# untitled.net
KiCad netlist of a schematic drawn in EAGLE
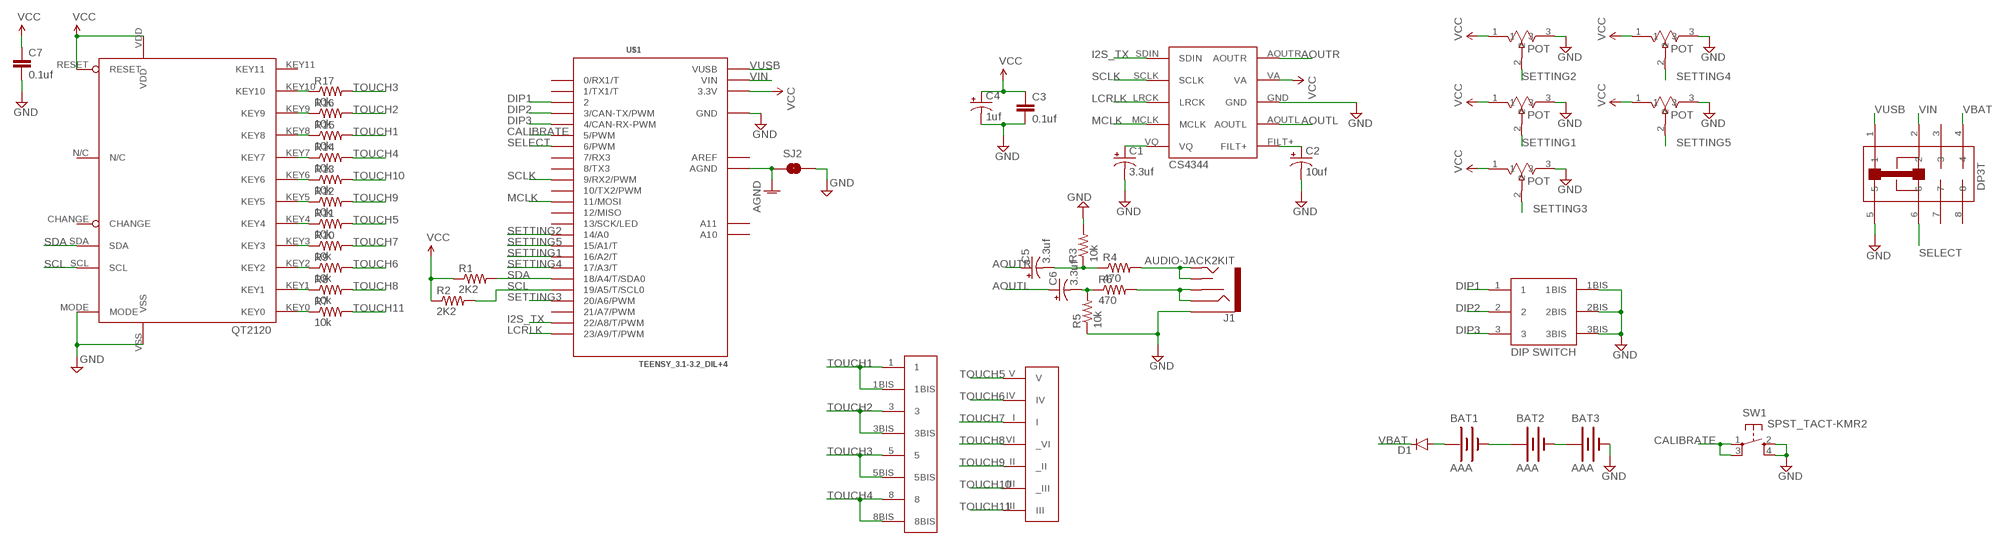
[diagram p0: schematic, sheet 1]

(export (version "E")
  (design (tool "Eeschema 10.0.6"))
  (components
    (comp (ref "BAT1")
      (value "AAA")
      (footprint "eagle-import:BATTERY-AAA-KIT")
      (libsource (lib "eagle-import") (part "BATTERYAAA-KIT"))
    )
    (comp (ref "BAT2")
      (value "AAA")
      (footprint "eagle-import:BATTERY-AAA-KIT")
      (libsource (lib "eagle-import") (part "BATTERYAAA-KIT"))
    )
    (comp (ref "BAT3")
      (value "AAA")
      (footprint "eagle-import:BATTERY-AAA-KIT")
      (libsource (lib "eagle-import") (part "BATTERYAAA-KIT"))
    )
    (comp (ref "C1")
      (value "3.3uf")
      (footprint "eagle-import:EIA3216")
      (libsource (lib "eagle-import") (part "CAP_POL1206"))
    )
    (comp (ref "C2")
      (value "10uf")
      (footprint "eagle-import:EIA3216")
      (libsource (lib "eagle-import") (part "CAP_POL1206"))
    )
    (comp (ref "C3")
      (value "0.1uf")
      (footprint "eagle-import:1206")
      (libsource (lib "eagle-import") (part "CAP1206"))
    )
    (comp (ref "C4")
      (value "1uf")
      (footprint "eagle-import:EIA3216")
      (libsource (lib "eagle-import") (part "SparkFun-Passives_CAP_POL1206"))
    )
    (comp (ref "C5")
      (value "3.3uf")
      (footprint "eagle-import:EIA3216")
      (libsource (lib "eagle-import") (part "SparkFun-Passives_CAP_POL1206"))
    )
    (comp (ref "C6")
      (value "3.3uf")
      (footprint "eagle-import:EIA3216")
      (libsource (lib "eagle-import") (part "SparkFun-Passives_CAP_POL1206"))
    )
    (comp (ref "C7")
      (value "0.1uf")
      (footprint "eagle-import:1206")
      (libsource (lib "eagle-import") (part "CAP1206"))
    )
    (comp (ref "D1")
      (value "DIODESOD123")
      (footprint "eagle-import:SOD-123")
      (libsource (lib "eagle-import") (part "DIODESOD123"))
    )
    (comp (ref "DIP1")
      (value "SDA03H1BD")
      (footprint "eagle-import:SDA03H1BD")
      (libsource (lib "eagle-import") (part "SDA03H1BD"))
    )
    (comp (ref "DP3T1")
      (value "OS203012MU5QP1")
      (footprint "eagle-import:OS203012MU5QP1")
      (libsource (lib "eagle-import") (part "OS203012MU5QP1"))
    )
    (comp (ref "J1")
      (value "AUDIO-JACK2KIT")
      (footprint "eagle-import:AUDIO-JACK-KIT")
      (libsource (lib "eagle-import") (part "AUDIO-JACK2KIT"))
    )
    (comp (ref "POT2")
      (value "PTV09A-4020U-B104")
      (footprint "eagle-import:PTV09A-4020U-B104")
      (libsource (lib "eagle-import") (part "PTV09A-4020U-B104"))
    )
    (comp (ref "POT3")
      (value "PTV09A-4020U-B104")
      (footprint "eagle-import:PTV09A-4020U-B104")
      (libsource (lib "eagle-import") (part "PTV09A-4020U-B104"))
    )
    (comp (ref "POT5")
      (value "PTV09A-4020U-B104")
      (footprint "eagle-import:PTV09A-4020U-B104")
      (libsource (lib "eagle-import") (part "PTV09A-4020U-B104"))
    )
    (comp (ref "R1")
      (value "2K2")
      (footprint "eagle-import:1206")
      (libsource (lib "eagle-import") (part "RESISTOR1206"))
    )
    (comp (ref "R2")
      (value "2K2")
      (footprint "eagle-import:1206")
      (libsource (lib "eagle-import") (part "RESISTOR1206"))
    )
    (comp (ref "R3")
      (value "10k")
      (footprint "eagle-import:1206")
      (libsource (lib "eagle-import") (part "RESISTOR1206"))
    )
    (comp (ref "R4")
      (value "470")
      (footprint "eagle-import:1206")
      (libsource (lib "eagle-import") (part "RESISTOR1206"))
    )
    (comp (ref "R5")
      (value "10k")
      (footprint "eagle-import:1206")
      (libsource (lib "eagle-import") (part "RESISTOR1206"))
    )
    (comp (ref "R6")
      (value "470")
      (footprint "eagle-import:1206")
      (libsource (lib "eagle-import") (part "RESISTOR1206"))
    )
    (comp (ref "R7")
      (value "10k")
      (footprint "eagle-import:1206")
      (libsource (lib "eagle-import") (part "RESISTOR1206"))
    )
    (comp (ref "R8")
      (value "10k")
      (footprint "eagle-import:1206")
      (libsource (lib "eagle-import") (part "RESISTOR1206"))
    )
    (comp (ref "R9")
      (value "10k")
      (footprint "eagle-import:1206")
      (libsource (lib "eagle-import") (part "RESISTOR1206"))
    )
    (comp (ref "R10")
      (value "10k")
      (footprint "eagle-import:1206")
      (libsource (lib "eagle-import") (part "RESISTOR1206"))
    )
    (comp (ref "R11")
      (value "10k")
      (footprint "eagle-import:1206")
      (libsource (lib "eagle-import") (part "RESISTOR1206"))
    )
    (comp (ref "R12")
      (value "10k")
      (footprint "eagle-import:1206")
      (libsource (lib "eagle-import") (part "RESISTOR1206"))
    )
    (comp (ref "R13")
      (value "10k")
      (footprint "eagle-import:1206")
      (libsource (lib "eagle-import") (part "RESISTOR1206"))
    )
    (comp (ref "R14")
      (value "10k")
      (footprint "eagle-import:1206")
      (libsource (lib "eagle-import") (part "RESISTOR1206"))
    )
    (comp (ref "R15")
      (value "10k")
      (footprint "eagle-import:1206")
      (libsource (lib "eagle-import") (part "RESISTOR1206"))
    )
    (comp (ref "R16")
      (value "10k")
      (footprint "eagle-import:1206")
      (libsource (lib "eagle-import") (part "RESISTOR1206"))
    )
    (comp (ref "R17")
      (value "10k")
      (footprint "eagle-import:1206")
      (libsource (lib "eagle-import") (part "RESISTOR1206"))
    )
    (comp (ref "SJ2")
      (value "JUMPER-PAD-2-NC_BY_TRACE")
      (footprint "eagle-import:PAD-JUMPER-2-NC_BY_TRACE_YES_SILK")
      (libsource (lib "eagle-import") (part "JUMPER-PAD-2-NC_BY_TRACE"))
    )
    (comp (ref "SW1")
      (value "SPST_TACT-KMR2")
      (footprint "eagle-import:KMR2")
      (libsource (lib "eagle-import") (part "SPST_TACT-KMR2"))
    )
    (comp (ref "SWEEP")
      (value "PTV09A-4020U-B104")
      (footprint "eagle-import:PTV09A-4020U-B104")
      (libsource (lib "eagle-import") (part "PTV09A-4020U-B104"))
    )
    (comp (ref "U$1")
      (value "TEENSY_3.1-3.2_DIL+4")
      (footprint "eagle-import:TEENSY_3.0-3.2&LC_DIL+4")
      (libsource (lib "eagle-import") (part "TEENSY_3.1-3.2_DIL+4"))
    )
    (comp (ref "U$2")
      (value "QT2120")
      (footprint "eagle-import:QT2120")
      (libsource (lib "eagle-import") (part "QT2120"))
    )
    (comp (ref "U$4")
      (value "NOTEPAD")
      (footprint "eagle-import:NOTEPAD")
      (libsource (lib "eagle-import") (part "NOTEPAD"))
    )
    (comp (ref "U$5")
      (value "CHORDPAD")
      (footprint "eagle-import:CHORDPAD")
      (libsource (lib "eagle-import") (part "CHORDPAD"))
    )
    (comp (ref "U1")
      (value "CS4344")
      (footprint "eagle-import:CS4344")
      (libsource (lib "eagle-import") (part "CS4344"))
    )
    (comp (ref "VOLUME")
      (value "PTV09A-4020U-B104")
      (footprint "eagle-import:PTV09A-4020U-B104")
      (libsource (lib "eagle-import") (part "PTV09A-4020U-B104"))
    )
  )
  (nets
    (net (code "1") (name "/AOUTL") (class "Default")
      (node (ref "C6") (pin "A") (pinfunction "+_A") (pintype "passive"))
      (node (ref "U1") (pin "AOUTL") (pinfunction "AOUTL_AOUTL") (pintype "bidirectional"))
    )
    (net (code "2") (name "/AOUTR") (class "Default")
      (node (ref "C5") (pin "A") (pinfunction "+_A") (pintype "passive"))
      (node (ref "U1") (pin "AOUTR") (pinfunction "AOUTR_AOUTR") (pintype "bidirectional"))
    )
    (net (code "3") (name "/AREF") (class "Default")
      (node (ref "U$1") (pin "AREF") (pinfunction "AREF_AREF") (pintype "power_in"))
    )
    (net (code "4") (name "/CALIBRATE") (class "Default")
      (node (ref "SW1") (pin "1") (pinfunction "P_1") (pintype "passive"))
      (node (ref "SW1") (pin "3") (pinfunction "P1_3") (pintype "passive"))
      (node (ref "U$1") (pin "5") (pinfunction "5/PWM_5") (pintype "bidirectional"))
    )
    (net (code "5") (name "/DIP1") (class "Default")
      (node (ref "DIP1") (pin "1") (pinfunction "1_1") (pintype "bidirectional"))
      (node (ref "U$1") (pin "2") (pinfunction "2_2") (pintype "bidirectional"))
    )
    (net (code "6") (name "/DIP2") (class "Default")
      (node (ref "DIP1") (pin "2") (pinfunction "2_2") (pintype "bidirectional"))
      (node (ref "U$1") (pin "3") (pinfunction "3/CAN-TX/PWM_3") (pintype "bidirectional"))
    )
    (net (code "7") (name "/DIP3") (class "Default")
      (node (ref "DIP1") (pin "3") (pinfunction "3_3") (pintype "bidirectional"))
      (node (ref "U$1") (pin "4") (pinfunction "4/CAN-RX-PWM_4") (pintype "bidirectional"))
    )
    (net (code "8") (name "/I2S_TX") (class "Default")
      (node (ref "U$1") (pin "22/A8") (pinfunction "22/A8/T/PWM_22/A8") (pintype "bidirectional"))
      (node (ref "U1") (pin "SDIN") (pinfunction "SDIN_SDIN") (pintype "bidirectional"))
    )
    (net (code "9") (name "/LCRLK") (class "Default")
      (node (ref "U$1") (pin "23/A9") (pinfunction "23/A9/T/PWM_23/A9") (pintype "bidirectional"))
      (node (ref "U1") (pin "LRCK") (pinfunction "LRCK_LRCK") (pintype "bidirectional"))
    )
    (net (code "10") (name "/MCLK") (class "Default")
      (node (ref "U$1") (pin "11") (pinfunction "11/MOSI_11") (pintype "bidirectional"))
      (node (ref "U1") (pin "MCLK") (pinfunction "MCLK_MCLK") (pintype "bidirectional"))
    )
    (net (code "11") (name "/SCL") (class "Default")
      (node (ref "R2") (pin "2") (pinfunction "2_2") (pintype "passive"))
      (node (ref "U$1") (pin "19/A5") (pinfunction "19/A5/T/SCL0_19/A5") (pintype "bidirectional"))
      (node (ref "U$2") (pin "SCL") (pinfunction "SCL_SCL") (pintype "bidirectional"))
    )
    (net (code "12") (name "/SCLK") (class "Default")
      (node (ref "U$1") (pin "9") (pinfunction "9/RX2/PWM_9") (pintype "bidirectional"))
      (node (ref "U1") (pin "SCLK") (pinfunction "SCLK_SCLK") (pintype "bidirectional"))
    )
    (net (code "13") (name "/SDA") (class "Default")
      (node (ref "R1") (pin "2") (pinfunction "2_2") (pintype "passive"))
      (node (ref "U$1") (pin "18/A4") (pinfunction "18/A4/T/SDA0_18/A4") (pintype "bidirectional"))
      (node (ref "U$2") (pin "SDA") (pinfunction "SDA_SDA") (pintype "bidirectional"))
    )
    (net (code "14") (name "/SELECT") (class "Default")
      (node (ref "DP3T1") (pin "6") (pinfunction "6_6") (pintype "bidirectional"))
      (node (ref "U$1") (pin "6") (pinfunction "6/PWM_6") (pintype "bidirectional"))
    )
    (net (code "15") (name "/SETTING1") (class "Default")
      (node (ref "POT2") (pin "2") (pinfunction "2_2") (pintype "bidirectional"))
      (node (ref "U$1") (pin "16/A2") (pinfunction "16/A2/T_16/A2") (pintype "bidirectional"))
    )
    (net (code "16") (name "/SETTING2") (class "Default")
      (node (ref "U$1") (pin "14/A0") (pinfunction "14/A0_14/A0") (pintype "bidirectional"))
      (node (ref "VOLUME") (pin "2") (pinfunction "2_2") (pintype "bidirectional"))
    )
    (net (code "17") (name "/SETTING3") (class "Default")
      (node (ref "POT3") (pin "2") (pinfunction "2_2") (pintype "bidirectional"))
      (node (ref "U$1") (pin "20/A6") (pinfunction "20/A6/PWM_20/A6") (pintype "bidirectional"))
    )
    (net (code "18") (name "/SETTING4") (class "Default")
      (node (ref "SWEEP") (pin "2") (pinfunction "2_2") (pintype "bidirectional"))
      (node (ref "U$1") (pin "17/A3") (pinfunction "17/A3/T_17/A3") (pintype "bidirectional"))
    )
    (net (code "19") (name "/SETTING5") (class "Default")
      (node (ref "POT5") (pin "2") (pinfunction "2_2") (pintype "bidirectional"))
      (node (ref "U$1") (pin "15/A1") (pinfunction "15/A1/T_15/A1") (pintype "bidirectional"))
    )
    (net (code "20") (name "/TOUCH1") (class "Default")
      (node (ref "R15") (pin "2") (pinfunction "2_2") (pintype "passive"))
      (node (ref "U$4") (pin "1") (pinfunction "1_1") (pintype "bidirectional"))
      (node (ref "U$4") (pin "1BIS") (pinfunction "1BIS_1BIS") (pintype "bidirectional"))
    )
    (net (code "21") (name "/TOUCH2") (class "Default")
      (node (ref "R16") (pin "2") (pinfunction "2_2") (pintype "passive"))
      (node (ref "U$4") (pin "3") (pinfunction "3_3") (pintype "bidirectional"))
      (node (ref "U$4") (pin "3BIS") (pinfunction "3BIS_3BIS") (pintype "bidirectional"))
    )
    (net (code "22") (name "/TOUCH3") (class "Default")
      (node (ref "R17") (pin "2") (pinfunction "2_2") (pintype "passive"))
      (node (ref "U$4") (pin "5") (pinfunction "5_5") (pintype "bidirectional"))
      (node (ref "U$4") (pin "5BIS") (pinfunction "5BIS_5BIS") (pintype "bidirectional"))
    )
    (net (code "23") (name "/TOUCH4") (class "Default")
      (node (ref "R14") (pin "2") (pinfunction "2_2") (pintype "passive"))
      (node (ref "U$4") (pin "8") (pinfunction "8_8") (pintype "bidirectional"))
      (node (ref "U$4") (pin "8BIS") (pinfunction "8BIS_8BIS") (pintype "bidirectional"))
    )
    (net (code "24") (name "/TOUCH5") (class "Default")
      (node (ref "R11") (pin "2") (pinfunction "2_2") (pintype "passive"))
      (node (ref "U$5") (pin "V") (pinfunction "V_V") (pintype "bidirectional"))
    )
    (net (code "25") (name "/TOUCH6") (class "Default")
      (node (ref "R9") (pin "2") (pinfunction "2_2") (pintype "passive"))
      (node (ref "U$5") (pin "IV") (pinfunction "IV_IV") (pintype "bidirectional"))
    )
    (net (code "26") (name "/TOUCH7") (class "Default")
      (node (ref "R10") (pin "2") (pinfunction "2_2") (pintype "passive"))
      (node (ref "U$5") (pin "I") (pinfunction "I_I") (pintype "bidirectional"))
    )
    (net (code "27") (name "/TOUCH8") (class "Default")
      (node (ref "R8") (pin "2") (pinfunction "2_2") (pintype "passive"))
      (node (ref "U$5") (pin "_VI") (pinfunction "_VI__VI") (pintype "bidirectional"))
    )
    (net (code "28") (name "/TOUCH9") (class "Default")
      (node (ref "R12") (pin "2") (pinfunction "2_2") (pintype "passive"))
      (node (ref "U$5") (pin "_II") (pinfunction "_II__II") (pintype "bidirectional"))
    )
    (net (code "29") (name "/TOUCH10") (class "Default")
      (node (ref "R13") (pin "2") (pinfunction "2_2") (pintype "passive"))
      (node (ref "U$5") (pin "_III") (pinfunction "_III__III") (pintype "bidirectional"))
    )
    (net (code "30") (name "/TOUCH11") (class "Default")
      (node (ref "R7") (pin "2") (pinfunction "2_2") (pintype "passive"))
      (node (ref "U$5") (pin "III") (pinfunction "III_III") (pintype "bidirectional"))
    )
    (net (code "31") (name "/VBAT") (class "Default")
      (node (ref "D1") (pin "C") (pinfunction "C_C") (pintype "passive"))
      (node (ref "DP3T1") (pin "4") (pinfunction "4_4") (pintype "bidirectional"))
    )
    (net (code "32") (name "/VIN") (class "Default")
      (node (ref "DP3T1") (pin "2") (pinfunction "2_2") (pintype "bidirectional"))
      (node (ref "U$1") (pin "VIN") (pinfunction "VIN_VIN") (pintype "power_in"))
    )
    (net (code "33") (name "/VUSB") (class "Default")
      (node (ref "DP3T1") (pin "1") (pinfunction "1_1") (pintype "bidirectional"))
      (node (ref "U$1") (pin "VUSB") (pinfunction "VUSB_VUSB") (pintype "power_in"))
    )
    (net (code "34") (name "AGND") (class "Default")
      (node (ref "SJ2") (pin "1") (pinfunction "1_1") (pintype "passive"))
      (node (ref "U$1") (pin "AGND") (pinfunction "AGND_AGND") (pintype "power_in"))
    )
    (net (code "35") (name "GND") (class "Default")
      (node (ref "BAT3") (pin "GND@1") (pinfunction "-_GND@1") (pintype "power_in"))
      (node (ref "C1") (pin "C") (pinfunction "-_C") (pintype "passive"))
      (node (ref "C2") (pin "C") (pinfunction "-_C") (pintype "passive"))
      (node (ref "C3") (pin "2") (pinfunction "2_2") (pintype "passive"))
      (node (ref "C4") (pin "C") (pinfunction "-_C") (pintype "passive"))
      (node (ref "C7") (pin "2") (pinfunction "2_2") (pintype "passive"))
      (node (ref "DIP1") (pin "1BIS") (pinfunction "1BIS_1BIS") (pintype "bidirectional"))
      (node (ref "DIP1") (pin "2BIS") (pinfunction "2BIS_2BIS") (pintype "bidirectional"))
      (node (ref "DIP1") (pin "3BIS") (pinfunction "3BIS_3BIS") (pintype "bidirectional"))
      (node (ref "DP3T1") (pin "5") (pinfunction "5_5") (pintype "bidirectional"))
      (node (ref "J1") (pin "SLEEVE") (pinfunction "SLEEVE_SLEEVE") (pintype "bidirectional"))
      (node (ref "POT2") (pin "3") (pinfunction "3_3") (pintype "bidirectional"))
      (node (ref "POT3") (pin "3") (pinfunction "3_3") (pintype "bidirectional"))
      (node (ref "POT5") (pin "3") (pinfunction "3_3") (pintype "bidirectional"))
      (node (ref "R3") (pin "2") (pinfunction "2_2") (pintype "passive"))
      (node (ref "R5") (pin "1") (pinfunction "1_1") (pintype "passive"))
      (node (ref "SJ2") (pin "2") (pinfunction "2_2") (pintype "passive"))
      (node (ref "SW1") (pin "2") (pinfunction "S_2") (pintype "passive"))
      (node (ref "SW1") (pin "4") (pinfunction "S1_4") (pintype "passive"))
      (node (ref "SWEEP") (pin "3") (pinfunction "3_3") (pintype "bidirectional"))
      (node (ref "U$1") (pin "GND") (pinfunction "GND_GND") (pintype "power_in"))
      (node (ref "U$2") (pin "MODE") (pinfunction "MODE_MODE") (pintype "bidirectional"))
      (node (ref "U$2") (pin "VSS") (pinfunction "VSS_VSS") (pintype "bidirectional"))
      (node (ref "U1") (pin "GND") (pinfunction "GND_GND") (pintype "bidirectional"))
      (node (ref "VOLUME") (pin "3") (pinfunction "3_3") (pintype "bidirectional"))
    )
    (net (code "36") (name "Net-(BAT1-+)") (class "Default")
      (node (ref "BAT1") (pin "PWR@1") (pinfunction "+_PWR@1") (pintype "power_in"))
      (node (ref "D1") (pin "A") (pinfunction "A_A") (pintype "passive"))
    )
    (net (code "37") (name "Net-(BAT1--)") (class "Default")
      (node (ref "BAT1") (pin "GND@1") (pinfunction "-_GND@1") (pintype "power_in"))
      (node (ref "BAT2") (pin "PWR@1") (pinfunction "+_PWR@1") (pintype "power_in"))
    )
    (net (code "38") (name "Net-(BAT2--)") (class "Default")
      (node (ref "BAT2") (pin "GND@1") (pinfunction "-_GND@1") (pintype "power_in"))
      (node (ref "BAT3") (pin "PWR@1") (pinfunction "+_PWR@1") (pintype "power_in"))
    )
    (net (code "39") (name "Net-(C1-+)") (class "Default")
      (node (ref "C1") (pin "A") (pinfunction "+_A") (pintype "passive"))
      (node (ref "U1") (pin "VQ") (pinfunction "VQ_VQ") (pintype "bidirectional"))
    )
    (net (code "40") (name "Net-(C2-+)") (class "Default")
      (node (ref "C2") (pin "A") (pinfunction "+_A") (pintype "passive"))
      (node (ref "U1") (pin "FILT+") (pinfunction "FILT+_FILT+") (pintype "bidirectional"))
    )
    (net (code "41") (name "Net-(C5--)") (class "Default")
      (node (ref "C5") (pin "C") (pinfunction "-_C") (pintype "passive"))
      (node (ref "R3") (pin "1") (pinfunction "1_1") (pintype "passive"))
      (node (ref "R4") (pin "1") (pinfunction "1_1") (pintype "passive"))
    )
    (net (code "42") (name "Net-(C6--)") (class "Default")
      (node (ref "C6") (pin "C") (pinfunction "-_C") (pintype "passive"))
      (node (ref "R5") (pin "2") (pinfunction "2_2") (pintype "passive"))
      (node (ref "R6") (pin "1") (pinfunction "1_1") (pintype "passive"))
    )
    (net (code "43") (name "Net-(J1-PadRING)") (class "Default")
      (node (ref "J1") (pin "RING") (pinfunction "RING_RING") (pintype "bidirectional"))
      (node (ref "J1") (pin "RSH") (pinfunction "RSH_RSH") (pintype "bidirectional"))
      (node (ref "R6") (pin "2") (pinfunction "2_2") (pintype "passive"))
    )
    (net (code "44") (name "Net-(J1-PadTIP)") (class "Default")
      (node (ref "J1") (pin "TIP") (pinfunction "TIP_TIP") (pintype "bidirectional"))
      (node (ref "J1") (pin "TSH") (pinfunction "TSH_TSH") (pintype "bidirectional"))
      (node (ref "R4") (pin "2") (pinfunction "2_2") (pintype "passive"))
    )
    (net (code "45") (name "Net-(R7-Pad1)") (class "Default")
      (node (ref "R7") (pin "1") (pinfunction "1_1") (pintype "passive"))
      (node (ref "U$2") (pin "KEY0") (pinfunction "KEY0_KEY0") (pintype "bidirectional"))
    )
    (net (code "46") (name "Net-(R8-Pad1)") (class "Default")
      (node (ref "R8") (pin "1") (pinfunction "1_1") (pintype "passive"))
      (node (ref "U$2") (pin "KEY1") (pinfunction "KEY1_KEY1") (pintype "bidirectional"))
    )
    (net (code "47") (name "Net-(R9-Pad1)") (class "Default")
      (node (ref "R9") (pin "1") (pinfunction "1_1") (pintype "passive"))
      (node (ref "U$2") (pin "KEY2") (pinfunction "KEY2_KEY2") (pintype "bidirectional"))
    )
    (net (code "48") (name "Net-(R10-Pad1)") (class "Default")
      (node (ref "R10") (pin "1") (pinfunction "1_1") (pintype "passive"))
      (node (ref "U$2") (pin "KEY3") (pinfunction "KEY3_KEY3") (pintype "bidirectional"))
    )
    (net (code "49") (name "Net-(R11-Pad1)") (class "Default")
      (node (ref "R11") (pin "1") (pinfunction "1_1") (pintype "passive"))
      (node (ref "U$2") (pin "KEY4") (pinfunction "KEY4_KEY4") (pintype "bidirectional"))
    )
    (net (code "50") (name "Net-(R12-Pad1)") (class "Default")
      (node (ref "R12") (pin "1") (pinfunction "1_1") (pintype "passive"))
      (node (ref "U$2") (pin "KEY5") (pinfunction "KEY5_KEY5") (pintype "bidirectional"))
    )
    (net (code "51") (name "Net-(R13-Pad1)") (class "Default")
      (node (ref "R13") (pin "1") (pinfunction "1_1") (pintype "passive"))
      (node (ref "U$2") (pin "KEY6") (pinfunction "KEY6_KEY6") (pintype "bidirectional"))
    )
    (net (code "52") (name "Net-(R14-Pad1)") (class "Default")
      (node (ref "R14") (pin "1") (pinfunction "1_1") (pintype "passive"))
      (node (ref "U$2") (pin "KEY7") (pinfunction "KEY7_KEY7") (pintype "bidirectional"))
    )
    (net (code "53") (name "Net-(R15-Pad1)") (class "Default")
      (node (ref "R15") (pin "1") (pinfunction "1_1") (pintype "passive"))
      (node (ref "U$2") (pin "KEY8") (pinfunction "KEY8_KEY8") (pintype "bidirectional"))
    )
    (net (code "54") (name "Net-(R16-Pad1)") (class "Default")
      (node (ref "R16") (pin "1") (pinfunction "1_1") (pintype "passive"))
      (node (ref "U$2") (pin "KEY9") (pinfunction "KEY9_KEY9") (pintype "bidirectional"))
    )
    (net (code "55") (name "Net-(R17-Pad1)") (class "Default")
      (node (ref "R17") (pin "1") (pinfunction "1_1") (pintype "passive"))
      (node (ref "U$2") (pin "KEY10") (pinfunction "KEY10_KEY10") (pintype "bidirectional"))
    )
    (net (code "56") (name "VCC") (class "Default")
      (node (ref "C3") (pin "1") (pinfunction "1_1") (pintype "passive"))
      (node (ref "C4") (pin "A") (pinfunction "+_A") (pintype "passive"))
      (node (ref "C7") (pin "1") (pinfunction "1_1") (pintype "passive"))
      (node (ref "POT2") (pin "1") (pinfunction "1_1") (pintype "bidirectional"))
      (node (ref "POT3") (pin "1") (pinfunction "1_1") (pintype "bidirectional"))
      (node (ref "POT5") (pin "1") (pinfunction "1_1") (pintype "bidirectional"))
      (node (ref "R1") (pin "1") (pinfunction "1_1") (pintype "passive"))
      (node (ref "R2") (pin "1") (pinfunction "1_1") (pintype "passive"))
      (node (ref "SWEEP") (pin "1") (pinfunction "1_1") (pintype "bidirectional"))
      (node (ref "U$1") (pin "3.3V") (pinfunction "3.3V_3.3V") (pintype "power_in"))
      (node (ref "U$2") (pin "RESET") (pinfunction "RESET_RESET") (pintype "bidirectional"))
      (node (ref "U$2") (pin "VDD") (pinfunction "VDD_VDD") (pintype "bidirectional"))
      (node (ref "U1") (pin "VA") (pinfunction "VA_VA") (pintype "bidirectional"))
      (node (ref "VOLUME") (pin "1") (pinfunction "1_1") (pintype "bidirectional"))
    )
    (net (code "57") (name "unconnected-(DP3T1-Pad3)") (class "Default")
      (node (ref "DP3T1") (pin "3") (pinfunction "3_3") (pintype "bidirectional"))
    )
    (net (code "58") (name "unconnected-(DP3T1-Pad7)") (class "Default")
      (node (ref "DP3T1") (pin "7") (pinfunction "7_7") (pintype "bidirectional"))
    )
    (net (code "59") (name "unconnected-(DP3T1-Pad8)") (class "Default")
      (node (ref "DP3T1") (pin "8") (pinfunction "8_8") (pintype "bidirectional"))
    )
    (net (code "60") (name "unconnected-(U$1-0{slash}RX1{slash}T-Pad0)") (class "Default")
      (node (ref "U$1") (pin "0") (pinfunction "0/RX1/T_0") (pintype "bidirectional"))
    )
    (net (code "61") (name "unconnected-(U$1-1{slash}TX1{slash}T-Pad1)") (class "Default")
      (node (ref "U$1") (pin "1") (pinfunction "1/TX1/T_1") (pintype "bidirectional"))
    )
    (net (code "62") (name "unconnected-(U$1-7{slash}RX3-Pad7)") (class "Default")
      (node (ref "U$1") (pin "7") (pinfunction "7/RX3_7") (pintype "bidirectional"))
    )
    (net (code "63") (name "unconnected-(U$1-8{slash}TX3-Pad8)") (class "Default")
      (node (ref "U$1") (pin "8") (pinfunction "8/TX3_8") (pintype "bidirectional"))
    )
    (net (code "64") (name "unconnected-(U$1-10{slash}TX2{slash}PWM-Pad10)") (class "Default")
      (node (ref "U$1") (pin "10") (pinfunction "10/TX2/PWM_10") (pintype "bidirectional"))
    )
    (net (code "65") (name "unconnected-(U$1-12{slash}MISO-Pad12)") (class "Default")
      (node (ref "U$1") (pin "12") (pinfunction "12/MISO_12") (pintype "bidirectional"))
    )
    (net (code "66") (name "unconnected-(U$1-13{slash}SCK{slash}LED-Pad13)") (class "Default")
      (node (ref "U$1") (pin "13") (pinfunction "13/SCK/LED_13") (pintype "bidirectional"))
    )
    (net (code "67") (name "unconnected-(U$1-21{slash}A7{slash}PWM-Pad21{slash}A7)") (class "Default")
      (node (ref "U$1") (pin "21/A7") (pinfunction "21/A7/PWM_21/A7") (pintype "bidirectional"))
    )
    (net (code "68") (name "unconnected-(U$1-PadA10)") (class "Default")
      (node (ref "U$1") (pin "A10") (pinfunction "A10_A10") (pintype "bidirectional"))
    )
    (net (code "69") (name "unconnected-(U$1-PadA11)") (class "Default")
      (node (ref "U$1") (pin "A11") (pinfunction "A11_A11") (pintype "bidirectional"))
    )
    (net (code "70") (name "unconnected-(U$2-PadCHANGE)") (class "Default")
      (node (ref "U$2") (pin "CHANGE") (pinfunction "CHANGE_CHANGE") (pintype "bidirectional"))
    )
    (net (code "71") (name "unconnected-(U$2-PadKEY11)") (class "Default")
      (node (ref "U$2") (pin "KEY11") (pinfunction "KEY11_KEY11") (pintype "bidirectional"))
    )
    (net (code "72") (name "unconnected-(U$2-PadN{slash}C)") (class "Default")
      (node (ref "U$2") (pin "N/C") (pinfunction "N/C_N/C") (pintype "bidirectional"))
    )
  )
)
